# SCH_AP1_Sistema-Digitais_2026-10-01.net
KiCad netlist of a schematic drawn in EasyEDA
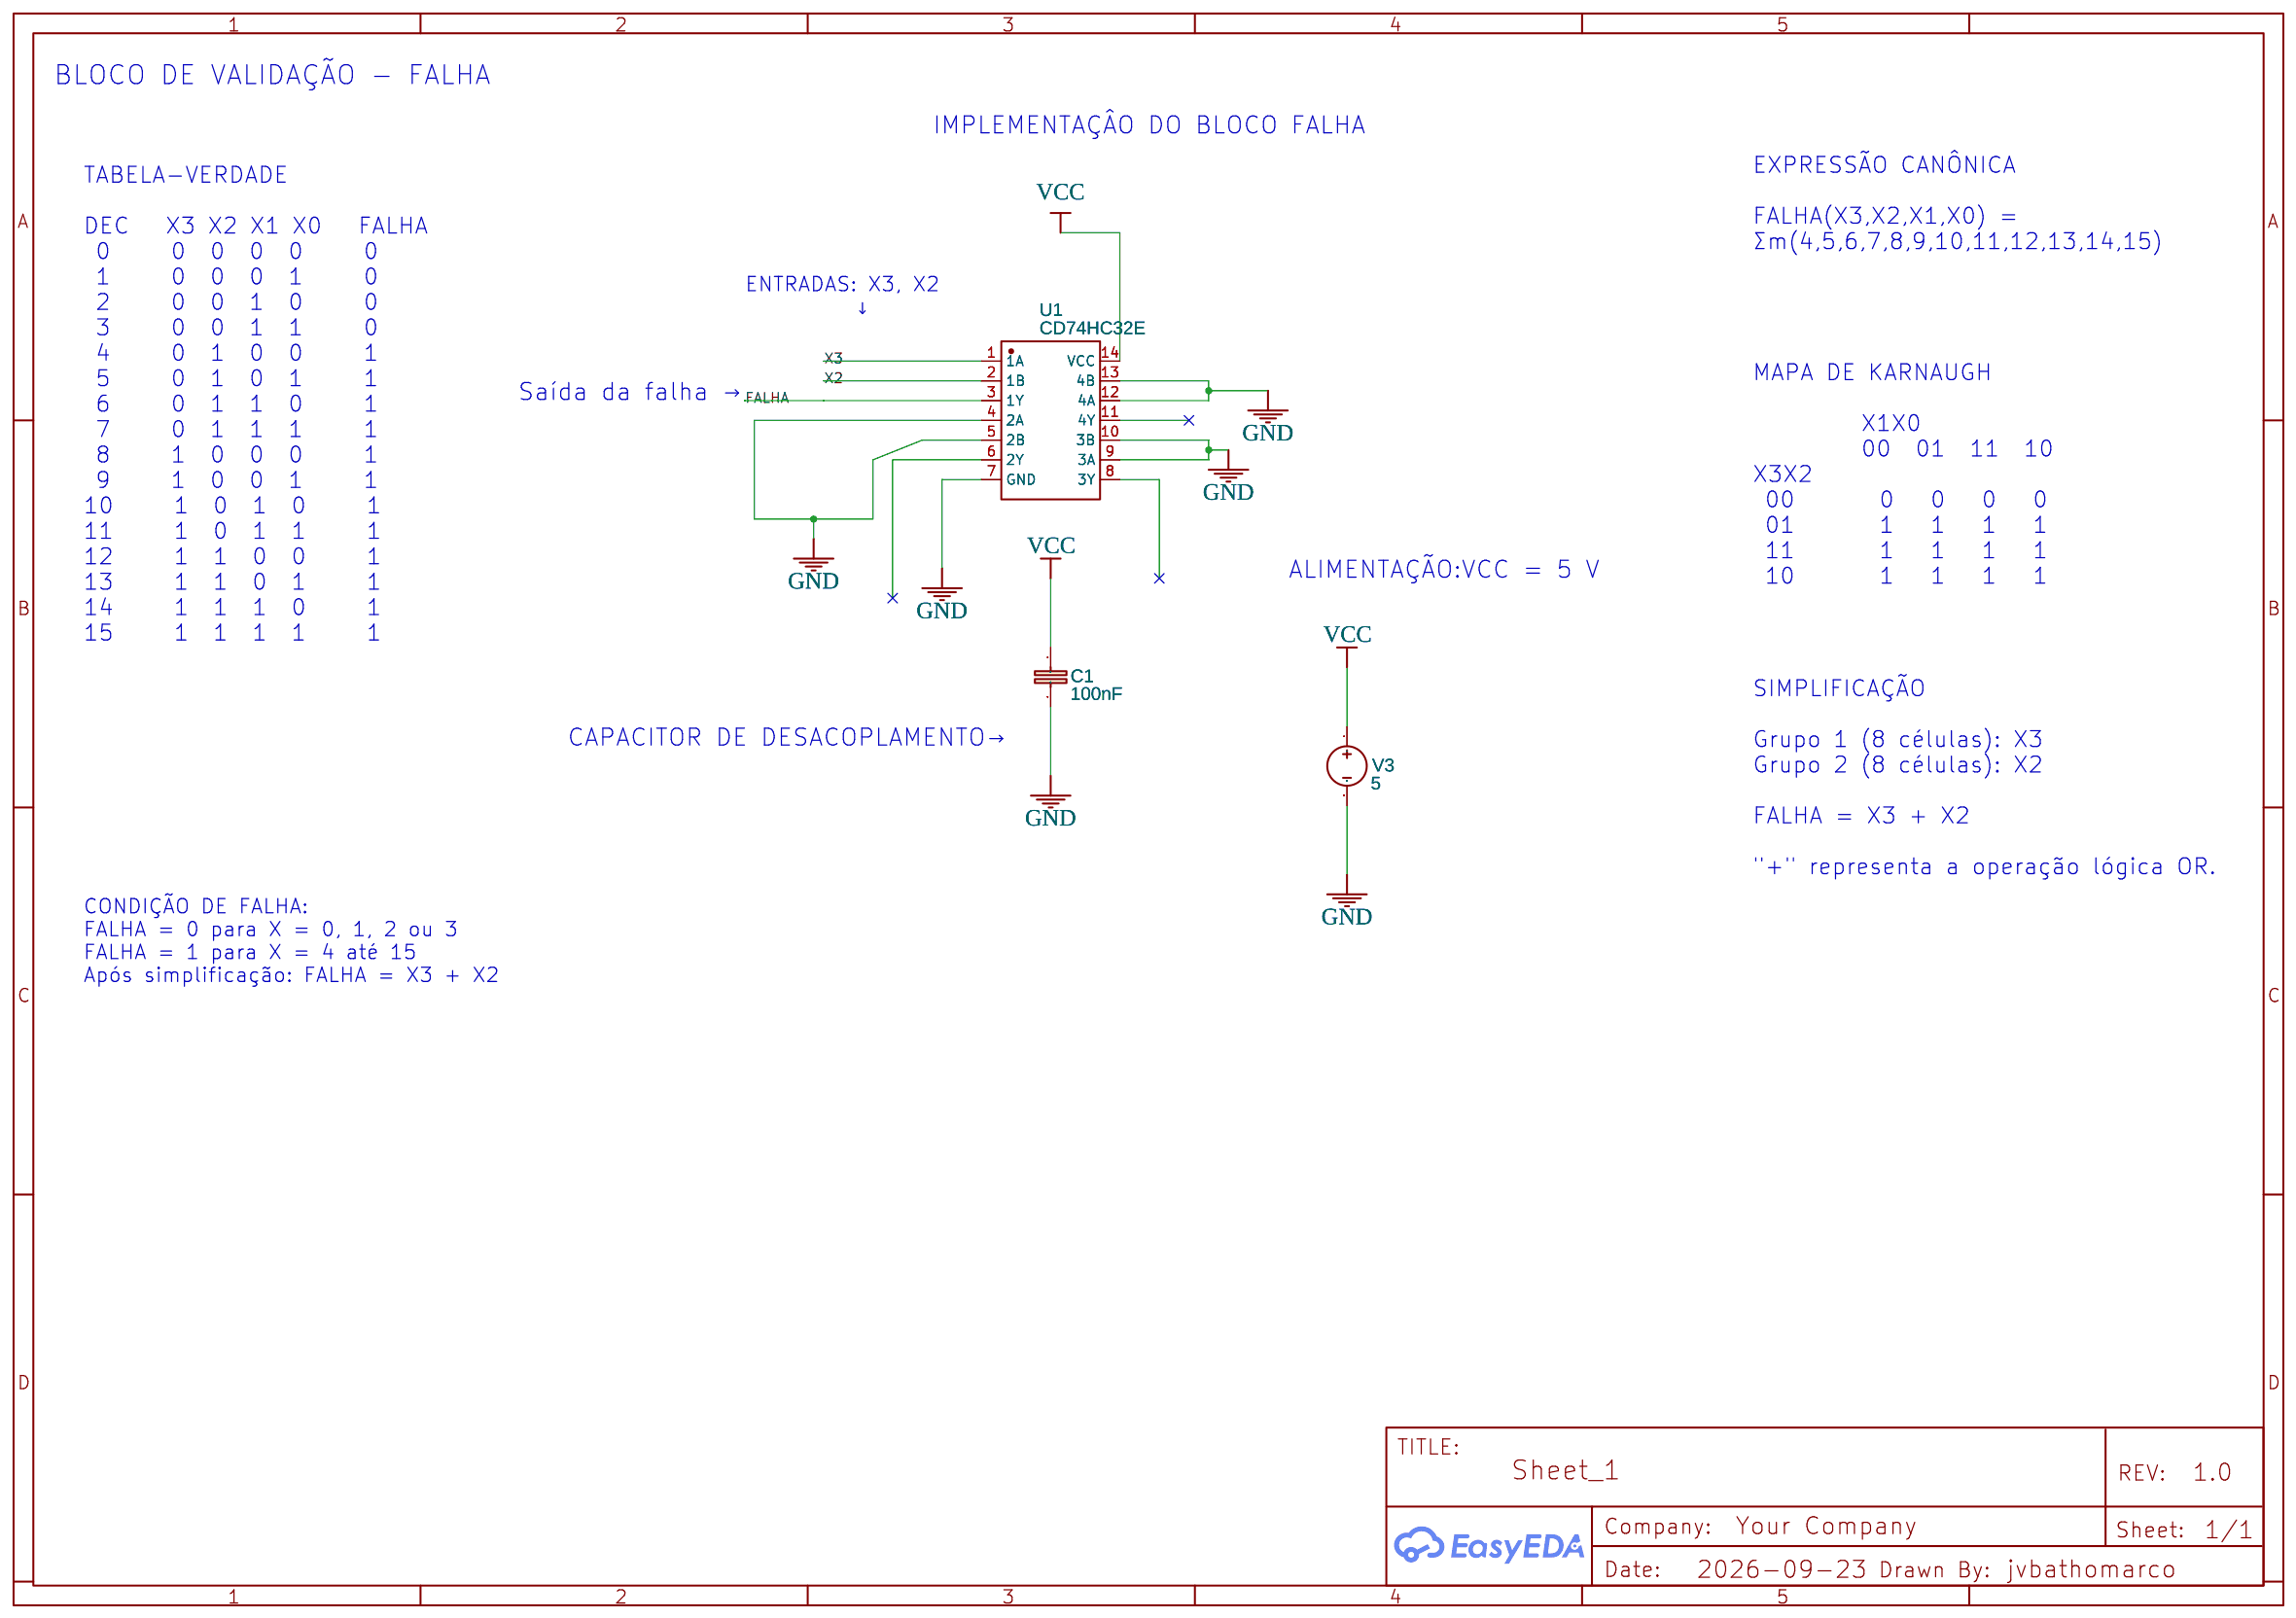
[diagram p0: Sheet_1]
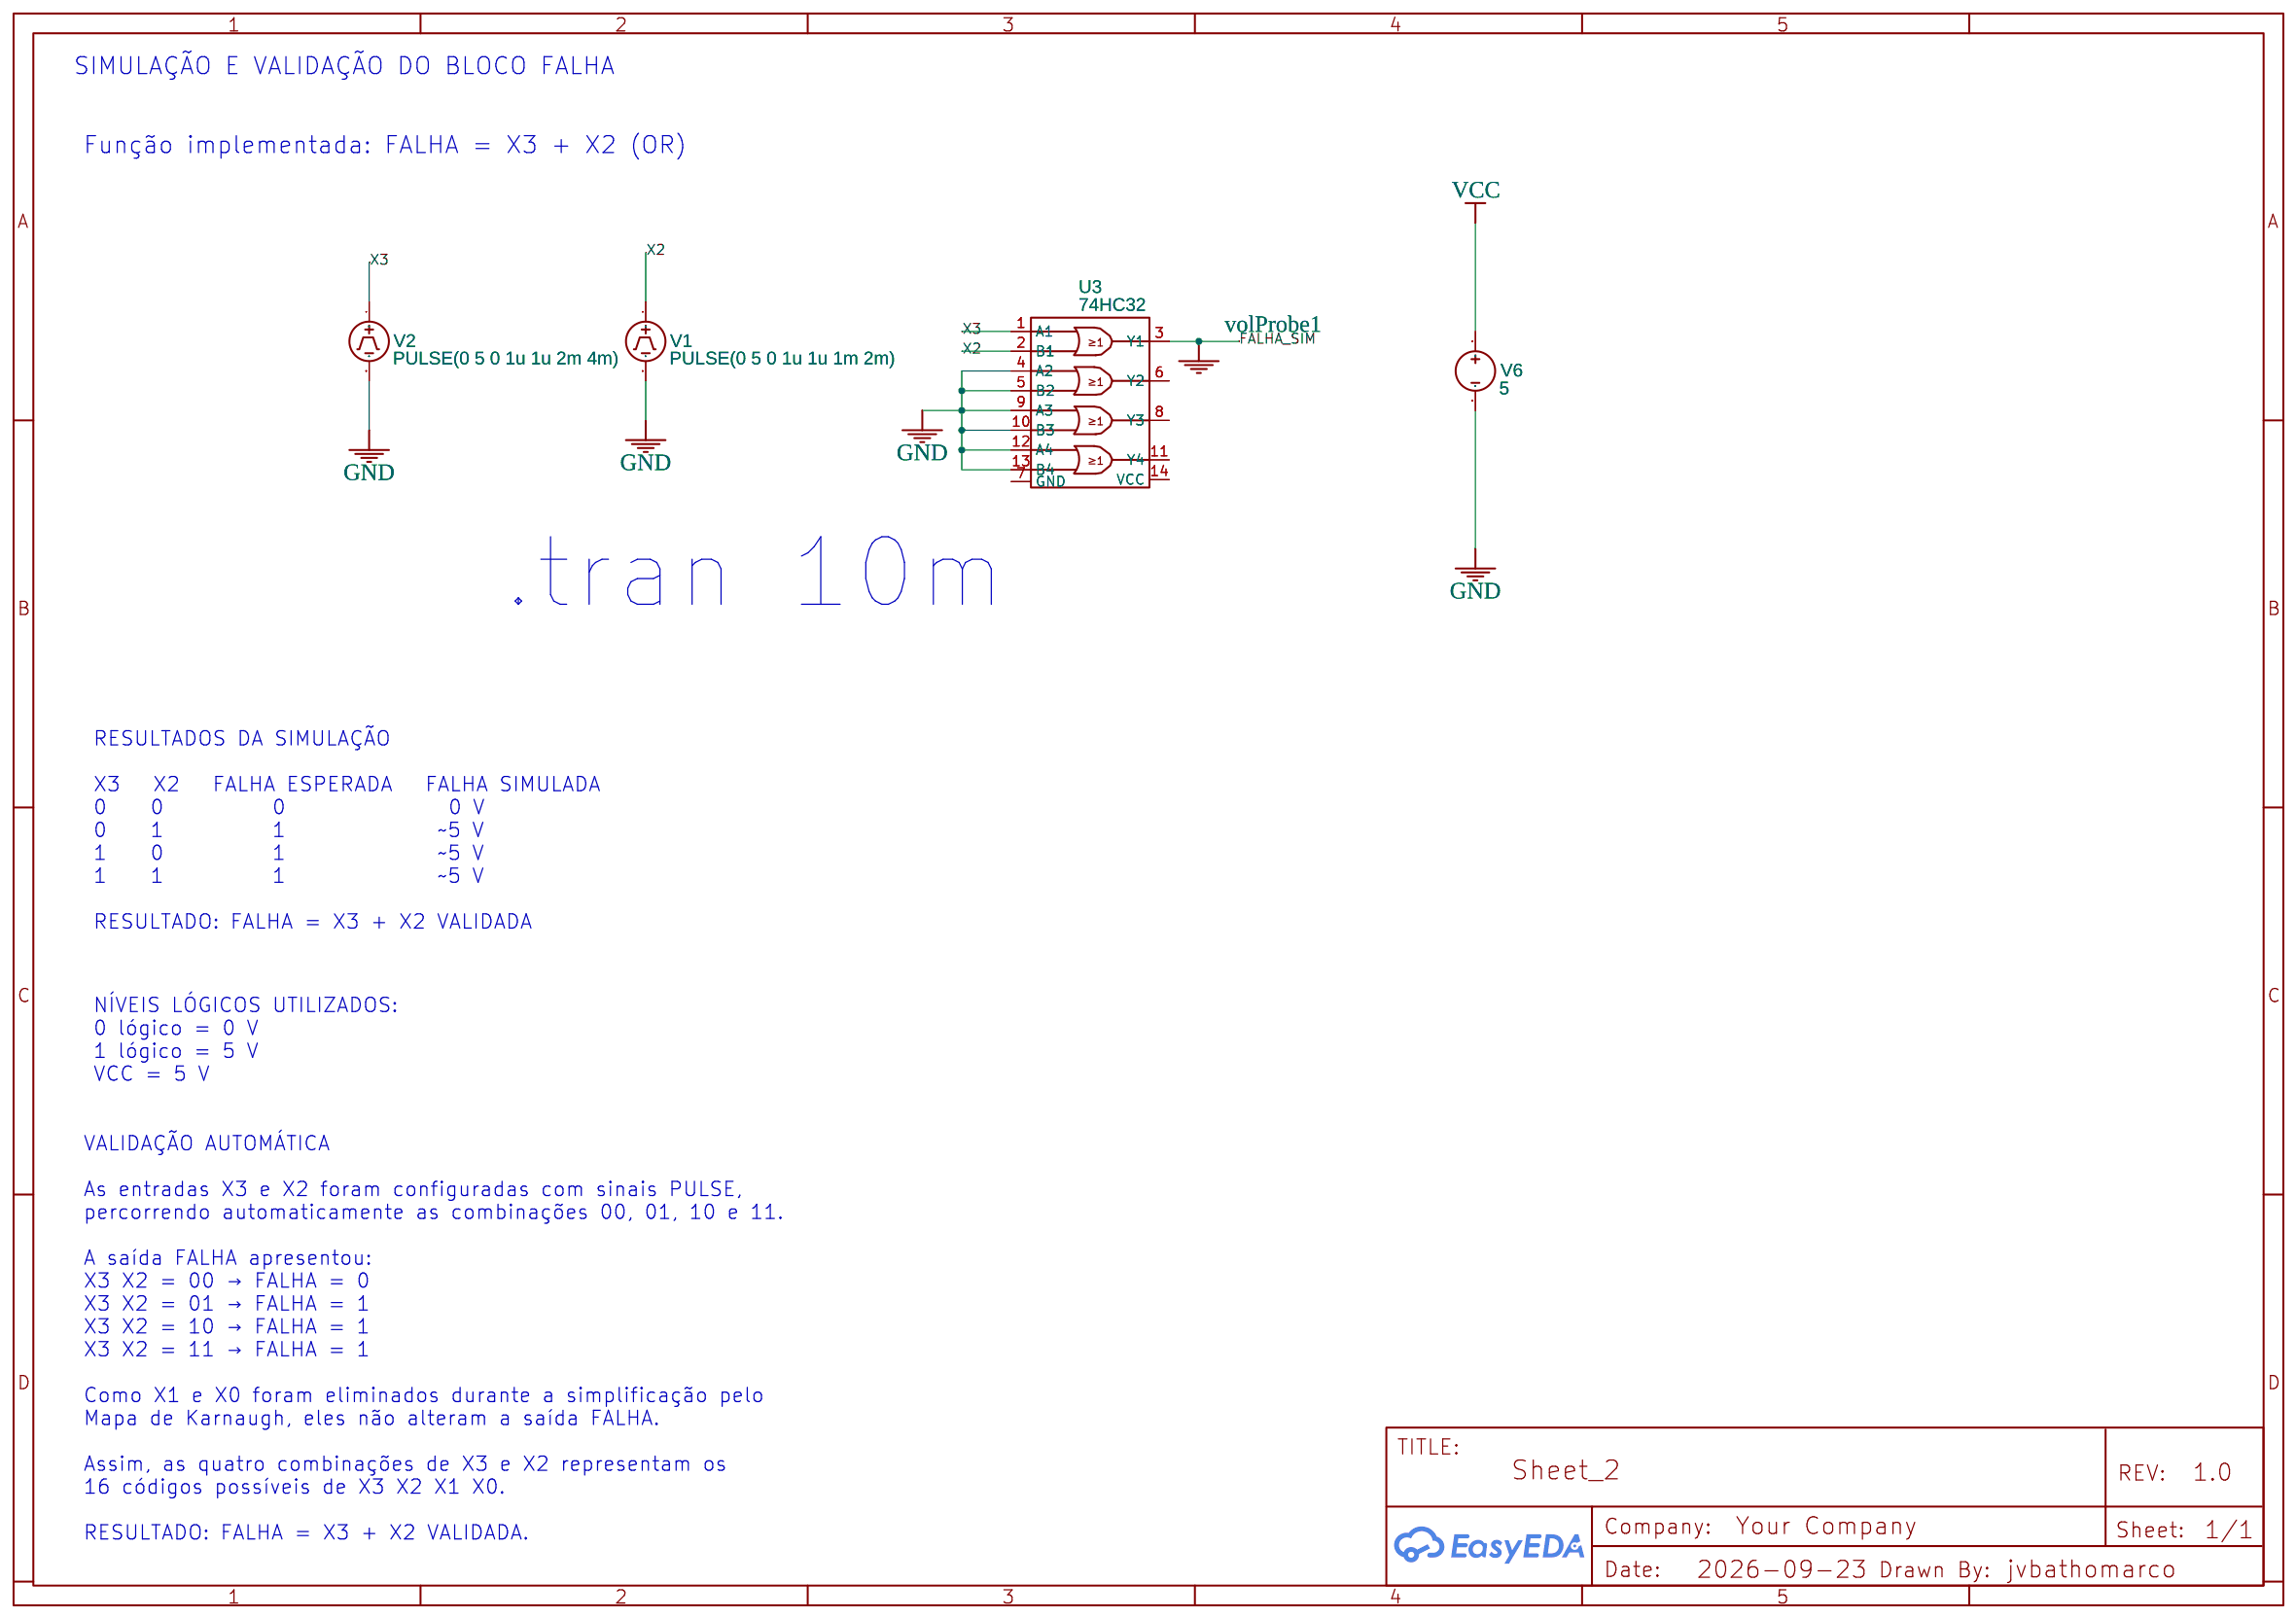
[diagram p1: Sheet_2]

(export (version "E")
  (design (tool "Eeschema 10.0.6"))
  (components
    (comp (ref "C1") (value "100nF") (libsource (lib "") (part "CAPACITOR_NPOL-PTH_0.1")))
    (comp (ref "U1")
      (value "CD74HC32E")
      (fields (field (name "Manufacturer") "TI(德州仪器)"))
      (libsource (lib "") (part "CD74HC32E"))
    )
    (comp (ref "V3") (value "5") (libsource (lib "") (part "VDC")))
    (comp (ref "U3") (value "74HC32") (libsource (lib "") (part "DIGITAL")))
    (comp (ref "V1") (value "PULSE(0 5 0 1u 1u 1m 2m)") (libsource (lib "") (part "VPULSE")))
    (comp (ref "V2") (value "PULSE(0 5 0 1u 1u 2m 4m)") (libsource (lib "") (part "VPULSE")))
    (comp (ref "V6") (value "5") (libsource (lib "") (part "VDC")))
  )
  (nets
    (net (code "1") (name "FALHA") (class "Default")
      (node (ref "U1") (pin "3") (pinfunction "1Y_3") (pintype "unspecified"))
    )
    (net (code "2") (name "FALHA_SIM") (class "Default")
      (node (ref "U3") (pin "3") (pinfunction "Y1_3") (pintype "unspecified"))
    )
    (net (code "3") (name "GND") (class "Default")
      (node (ref "C1") (pin "2") (pinfunction "2_2") (pintype "unspecified"))
      (node (ref "U1") (pin "10") (pinfunction "3B_10") (pintype "unspecified"))
      (node (ref "U1") (pin "12") (pinfunction "4A_12") (pintype "unspecified"))
      (node (ref "U1") (pin "13") (pinfunction "4B_13") (pintype "unspecified"))
      (node (ref "U1") (pin "4") (pinfunction "2A_4") (pintype "unspecified"))
      (node (ref "U1") (pin "5") (pinfunction "2B_5") (pintype "unspecified"))
      (node (ref "U1") (pin "7") (pinfunction "GND_7") (pintype "unspecified"))
      (node (ref "U1") (pin "9") (pinfunction "3A_9") (pintype "unspecified"))
      (node (ref "U3") (pin "10") (pinfunction "B3_10") (pintype "unspecified"))
      (node (ref "U3") (pin "12") (pinfunction "A4_12") (pintype "unspecified"))
      (node (ref "U3") (pin "13") (pinfunction "B4_13") (pintype "unspecified"))
      (node (ref "U3") (pin "4") (pinfunction "A2_4") (pintype "unspecified"))
      (node (ref "U3") (pin "5") (pinfunction "B2_5") (pintype "unspecified"))
      (node (ref "U3") (pin "9") (pinfunction "A3_9") (pintype "unspecified"))
      (node (ref "V1") (pin "2") (pinfunction "2_2") (pintype "unspecified"))
      (node (ref "V2") (pin "2") (pinfunction "2_2") (pintype "unspecified"))
      (node (ref "V3") (pin "2") (pinfunction "2_2") (pintype "unspecified"))
      (node (ref "V6") (pin "2") (pinfunction "2_2") (pintype "unspecified"))
    )
    (net (code "4") (name "VCC") (class "Default")
      (node (ref "C1") (pin "1") (pinfunction "1_1") (pintype "unspecified"))
      (node (ref "U1") (pin "14") (pinfunction "VCC_14") (pintype "unspecified"))
      (node (ref "V3") (pin "1") (pinfunction "1_1") (pintype "unspecified"))
      (node (ref "V6") (pin "1") (pinfunction "1_1") (pintype "unspecified"))
    )
    (net (code "5") (name "X2") (class "Default")
      (node (ref "U1") (pin "2") (pinfunction "1B_2") (pintype "unspecified"))
      (node (ref "U3") (pin "2") (pinfunction "B1_2") (pintype "unspecified"))
      (node (ref "V1") (pin "1") (pinfunction "1_1") (pintype "unspecified"))
    )
    (net (code "6") (name "X3") (class "Default")
      (node (ref "U1") (pin "1") (pinfunction "1A_1") (pintype "unspecified"))
      (node (ref "U3") (pin "1") (pinfunction "A1_1") (pintype "unspecified"))
      (node (ref "V2") (pin "1") (pinfunction "1_1") (pintype "unspecified"))
    )
    (net (code "7") (name "unconnected-(U1-2Y-Pad6)") (class "Default")
      (node (ref "U1") (pin "6") (pinfunction "2Y_6") (pintype "unspecified+no_connect"))
    )
    (net (code "8") (name "unconnected-(U1-3Y-Pad8)") (class "Default")
      (node (ref "U1") (pin "8") (pinfunction "3Y_8") (pintype "unspecified+no_connect"))
    )
    (net (code "9") (name "unconnected-(U1-4Y-Pad11)") (class "Default")
      (node (ref "U1") (pin "11") (pinfunction "4Y_11") (pintype "unspecified+no_connect"))
    )
    (net (code "10") (name "unconnected-(U3-GND-Pad7)") (class "Default")
      (node (ref "U3") (pin "7") (pinfunction "GND_7") (pintype "unspecified"))
    )
    (net (code "11") (name "unconnected-(U3-VCC-Pad14)") (class "Default")
      (node (ref "U3") (pin "14") (pinfunction "VCC_14") (pintype "unspecified"))
    )
    (net (code "12") (name "unconnected-(U3-Y2-Pad6)") (class "Default")
      (node (ref "U3") (pin "6") (pinfunction "Y2_6") (pintype "unspecified"))
    )
    (net (code "13") (name "unconnected-(U3-Y3-Pad8)") (class "Default")
      (node (ref "U3") (pin "8") (pinfunction "Y3_8") (pintype "unspecified"))
    )
    (net (code "14") (name "unconnected-(U3-Y4-Pad11)") (class "Default")
      (node (ref "U3") (pin "11") (pinfunction "Y4_11") (pintype "unspecified"))
    )
  )
)
